# telephon.net
KiCad netlist of a schematic drawn in EAGLE
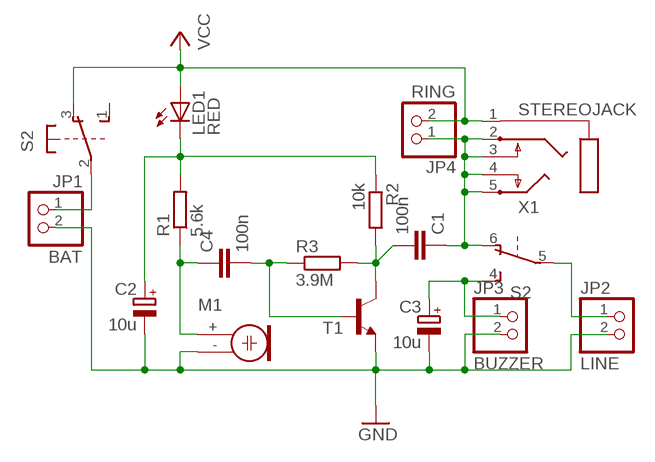
[diagram p0: schematic, sheet 1]

(export (version "E")
  (design (tool "Eeschema 10.0.6"))
  (components
    (comp (ref "C1")
      (value "100n")
      (footprint "eagle-import:C1206")
      (libsource (lib "eagle-import") (part "C-EUC1206"))
    )
    (comp (ref "C2")
      (value "10u")
      (footprint "eagle-import:B45181A")
      (libsource (lib "eagle-import") (part "CPOL-EUB45181A"))
    )
    (comp (ref "C3")
      (value "10u")
      (footprint "eagle-import:B45181A")
      (libsource (lib "eagle-import") (part "CPOL-EUB45181A"))
    )
    (comp (ref "C4")
      (value "100n")
      (footprint "eagle-import:C1206")
      (libsource (lib "eagle-import") (part "C-EUC1206"))
    )
    (comp (ref "JP1")
      (value "BAT")
      (footprint "eagle-import:1X02")
      (libsource (lib "eagle-import") (part "PINHD-1X2"))
    )
    (comp (ref "JP2")
      (value "LINE")
      (footprint "eagle-import:1X02")
      (libsource (lib "eagle-import") (part "PINHD-1X2"))
    )
    (comp (ref "JP3")
      (value "BUZZER")
      (footprint "eagle-import:1X02")
      (libsource (lib "eagle-import") (part "PINHD-1X2"))
    )
    (comp (ref "JP4")
      (value "RING")
      (footprint "eagle-import:1X02")
      (libsource (lib "eagle-import") (part "PINHD-1X2"))
    )
    (comp (ref "LED1")
      (value "RED")
      (footprint "eagle-import:LED5MM")
      (libsource (lib "eagle-import") (part "LED5MM"))
    )
    (comp (ref "M1")
      (value "ELECTRET")
      (footprint "eagle-import:9.7ELECTRET")
      (libsource (lib "eagle-import") (part "ELECTRET"))
    )
    (comp (ref "R1")
      (value "5.6k")
      (footprint "eagle-import:R1206")
      (libsource (lib "eagle-import") (part "R-EU_R1206"))
    )
    (comp (ref "R2")
      (value "10k")
      (footprint "eagle-import:R1206")
      (libsource (lib "eagle-import") (part "R-EU_R1206"))
    )
    (comp (ref "R3")
      (value "3.9M")
      (footprint "eagle-import:R1206")
      (libsource (lib "eagle-import") (part "R-EU_R1206"))
    )
    (comp (ref "S2")
      (value "9450-2")
      (footprint "eagle-import:9450-2")
      (libsource (lib "eagle-import") (part "9450-2"))
    )
    (comp (ref "T1")
      (value "MMBT2222ALT1-NPN-SOT23-BEC")
      (footprint "eagle-import:SOT23-BEC")
      (libsource (lib "eagle-import") (part "-NPN-SOT23-BECMMBT2222ALT1"))
    )
    (comp (ref "X1")
      (value "STEREOJACK")
      (footprint "eagle-import:STX3100")
      (libsource (lib "eagle-import") (part "STEREOJACK"))
    )
  )
  (nets
    (net (code "1") (name "GND") (class "Default")
      (node (ref "C2") (pin "-") (pinfunction "-_-") (pintype "passive"))
      (node (ref "C3") (pin "-") (pinfunction "-_-") (pintype "passive"))
      (node (ref "JP1") (pin "2") (pinfunction "2_2") (pintype "passive"))
      (node (ref "JP2") (pin "2") (pinfunction "2_2") (pintype "passive"))
      (node (ref "JP3") (pin "2") (pinfunction "2_2") (pintype "passive"))
      (node (ref "M1") (pin "-") (pinfunction "1_-") (pintype "passive"))
      (node (ref "T1") (pin "E") (pinfunction "E_E") (pintype "passive"))
    )
    (net (code "2") (name "Net-(C1-Pad2)") (class "Default")
      (node (ref "C1") (pin "2") (pinfunction "2_2") (pintype "passive"))
      (node (ref "R2") (pin "2") (pinfunction "2_2") (pintype "passive"))
      (node (ref "R3") (pin "2") (pinfunction "2_2") (pintype "passive"))
      (node (ref "T1") (pin "C") (pinfunction "C_C") (pintype "passive"))
    )
    (net (code "3") (name "Net-(C4-Pad2)") (class "Default")
      (node (ref "C4") (pin "2") (pinfunction "2_2") (pintype "passive"))
      (node (ref "R3") (pin "1") (pinfunction "1_1") (pintype "passive"))
      (node (ref "T1") (pin "B") (pinfunction "B_B") (pintype "passive"))
    )
    (net (code "4") (name "Net-(LED1-C)") (class "Default")
      (node (ref "C2") (pin "+") (pinfunction "+_+") (pintype "passive"))
      (node (ref "LED1") (pin "K") (pinfunction "C_K") (pintype "passive"))
      (node (ref "R1") (pin "2") (pinfunction "2_2") (pintype "passive"))
      (node (ref "R2") (pin "1") (pinfunction "1_1") (pintype "passive"))
    )
    (net (code "5") (name "Net-(M1-2)") (class "Default")
      (node (ref "C4") (pin "1") (pinfunction "1_1") (pintype "passive"))
      (node (ref "M1") (pin "+") (pinfunction "2_+") (pintype "passive"))
      (node (ref "R1") (pin "1") (pinfunction "1_1") (pintype "passive"))
    )
    (net (code "6") (name "Net-(S2A-P)") (class "Default")
      (node (ref "JP1") (pin "1") (pinfunction "1_1") (pintype "passive"))
      (node (ref "S2") (pin "2") (pinfunction "P_2") (pintype "passive"))
    )
    (net (code "7") (name "Net-(S2B-O)") (class "Default")
      (node (ref "C1") (pin "1") (pinfunction "1_1") (pintype "passive"))
      (node (ref "JP4") (pin "1") (pinfunction "1_1") (pintype "passive"))
      (node (ref "S2") (pin "6") (pinfunction "O_6") (pintype "passive"))
      (node (ref "X1") (pin "2") (pinfunction "2_2") (pintype "passive"))
      (node (ref "X1") (pin "3") (pinfunction "3_3") (pintype "passive"))
      (node (ref "X1") (pin "4") (pinfunction "4_4") (pintype "passive"))
      (node (ref "X1") (pin "5") (pinfunction "5_5") (pintype "passive"))
    )
    (net (code "8") (name "Net-(S2B-P)") (class "Default")
      (node (ref "JP2") (pin "1") (pinfunction "1_1") (pintype "passive"))
      (node (ref "S2") (pin "5") (pinfunction "P_5") (pintype "passive"))
    )
    (net (code "9") (name "Net-(S2B-S)") (class "Default")
      (node (ref "C3") (pin "+") (pinfunction "+_+") (pintype "passive"))
      (node (ref "JP3") (pin "1") (pinfunction "1_1") (pintype "passive"))
      (node (ref "S2") (pin "4") (pinfunction "S_4") (pintype "passive"))
    )
    (net (code "10") (name "VCC") (class "Default")
      (node (ref "JP4") (pin "2") (pinfunction "2_2") (pintype "passive"))
      (node (ref "LED1") (pin "A") (pinfunction "A_A") (pintype "passive"))
      (node (ref "S2") (pin "3") (pinfunction "O_3") (pintype "passive"))
      (node (ref "X1") (pin "1") (pinfunction "1_1") (pintype "passive"))
    )
    (net (code "11") (name "unconnected-(S2A-S-Pad1)") (class "Default")
      (node (ref "S2") (pin "1") (pinfunction "S_1") (pintype "passive"))
    )
  )
)
